# PwrSwHs1_0.net
KiCad netlist of a schematic drawn in EAGLE
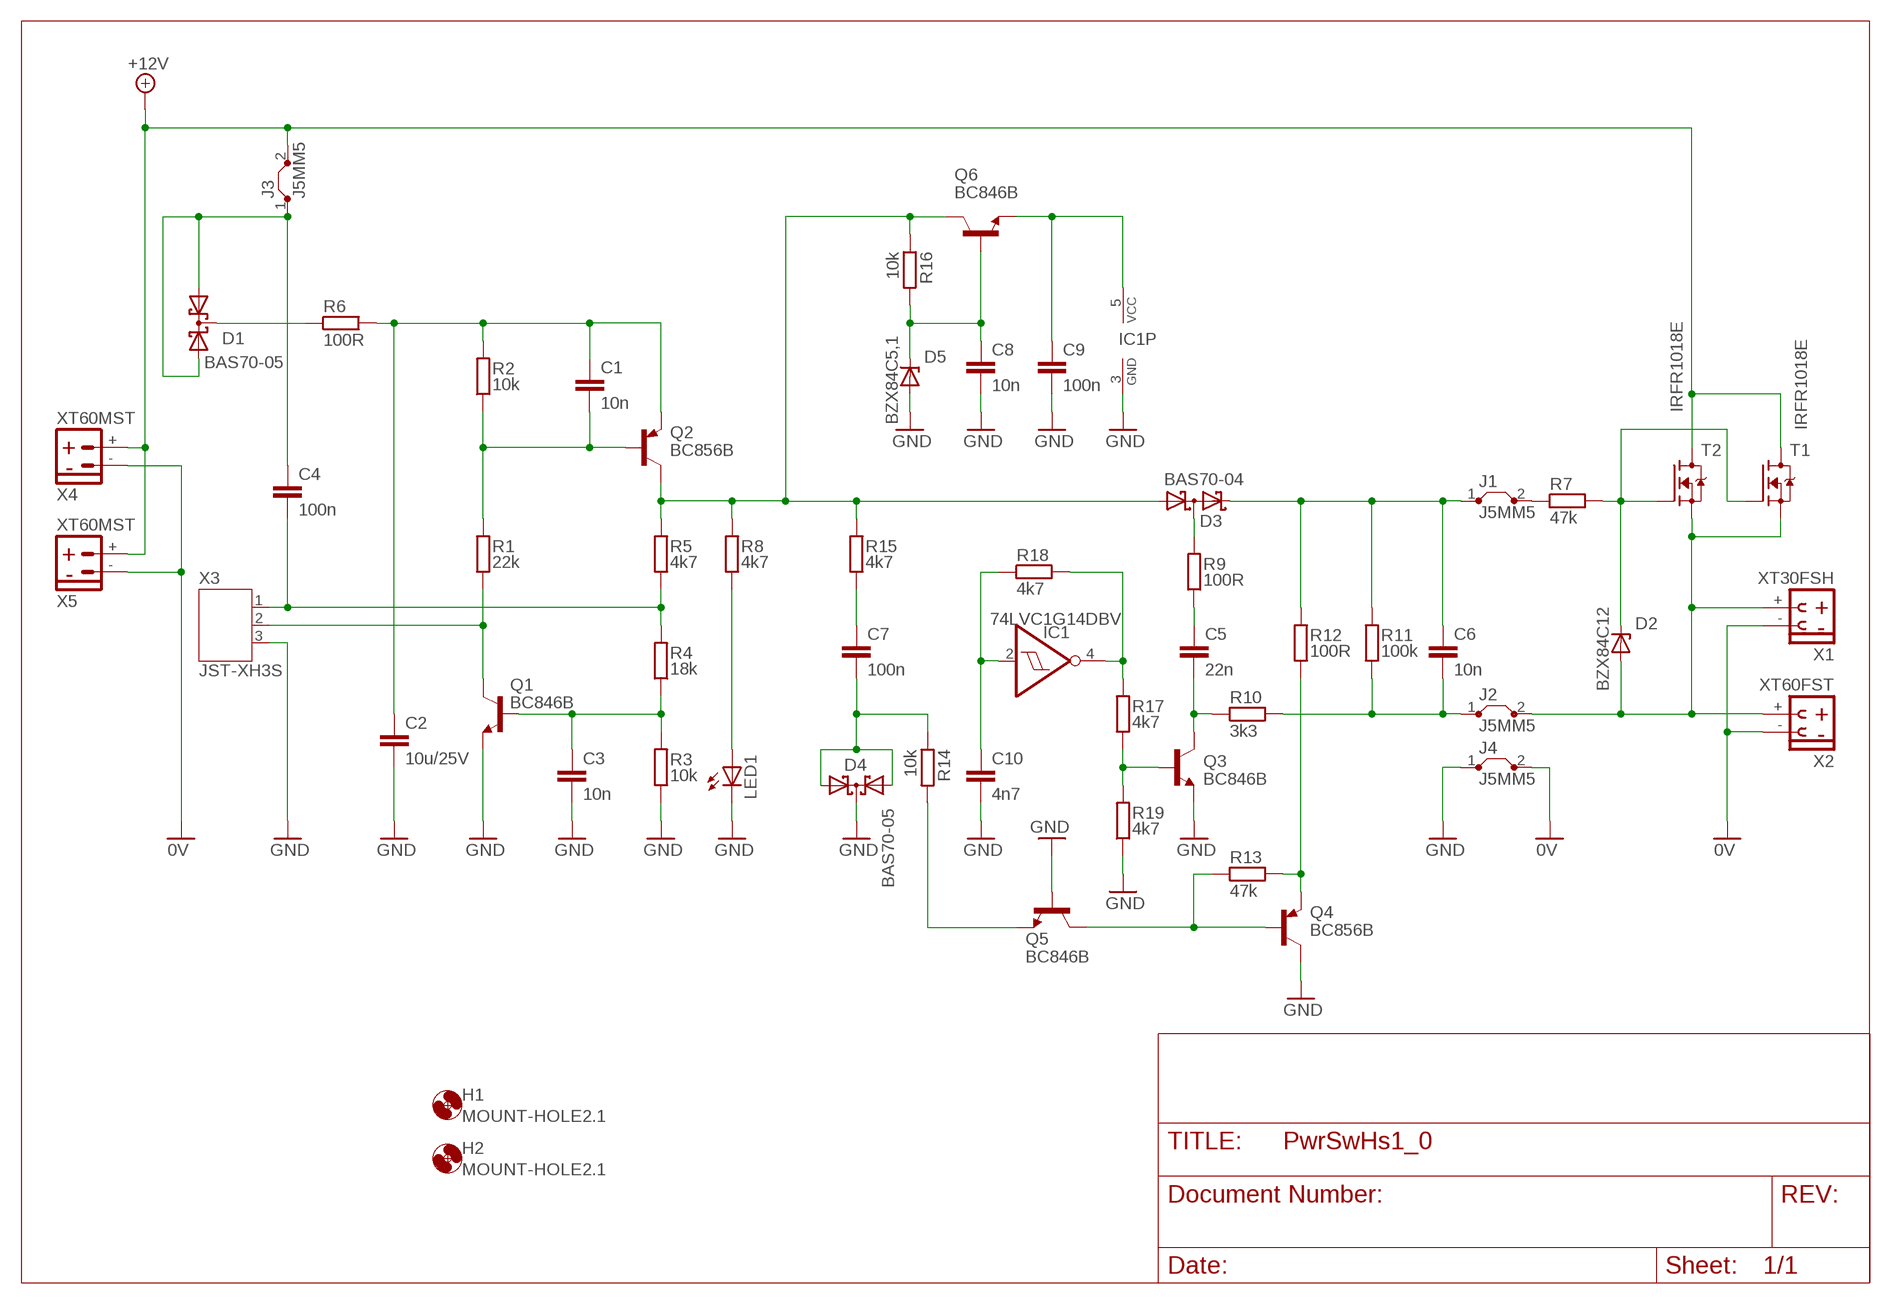
[diagram p0: schematic, sheet 1]

(export (version "E")
  (design (tool "Eeschema 10.0.6"))
  (components
    (comp (ref "C1")
      (value "10n")
      (footprint "eagle-import:C0805")
      (libsource (lib "eagle-import") (part "C-EUC0805"))
    )
    (comp (ref "C2")
      (value "10u/25V")
      (footprint "eagle-import:C1210")
      (libsource (lib "eagle-import") (part "C-EUC1210"))
    )
    (comp (ref "C3")
      (value "10n")
      (footprint "eagle-import:C0805")
      (libsource (lib "eagle-import") (part "C-EUC0805"))
    )
    (comp (ref "C4")
      (value "100n")
      (footprint "eagle-import:C0805")
      (libsource (lib "eagle-import") (part "C-EUC0805"))
    )
    (comp (ref "C5")
      (value "22n")
      (footprint "eagle-import:C0805")
      (libsource (lib "eagle-import") (part "C-EUC0805"))
    )
    (comp (ref "C6")
      (value "10n")
      (footprint "eagle-import:C0805")
      (libsource (lib "eagle-import") (part "C-EUC0805"))
    )
    (comp (ref "C7")
      (value "100n")
      (footprint "eagle-import:C0805")
      (libsource (lib "eagle-import") (part "C-EUC0805"))
    )
    (comp (ref "C8")
      (value "10n")
      (footprint "eagle-import:C0805")
      (libsource (lib "eagle-import") (part "C-EUC0805"))
    )
    (comp (ref "C9")
      (value "100n")
      (footprint "eagle-import:C0805")
      (libsource (lib "eagle-import") (part "C-EUC0805"))
    )
    (comp (ref "C10")
      (value "4n7")
      (footprint "eagle-import:C0805")
      (libsource (lib "eagle-import") (part "C-EUC0805"))
    )
    (comp (ref "D1")
      (value "BAS70-05")
      (footprint "eagle-import:SOT23")
      (libsource (lib "eagle-import") (part "BAS70-05"))
    )
    (comp (ref "D2")
      (value "BZX84C12")
      (footprint "eagle-import:TO236")
      (libsource (lib "eagle-import") (part "BZX84CSMD"))
    )
    (comp (ref "D3")
      (value "BAS70-04")
      (footprint "eagle-import:SOT23")
      (libsource (lib "eagle-import") (part "BAS70-04"))
    )
    (comp (ref "D4")
      (value "BAS70-05")
      (footprint "eagle-import:SOT23")
      (libsource (lib "eagle-import") (part "BAS70-05"))
    )
    (comp (ref "D5")
      (value "BZX84C5,1")
      (footprint "eagle-import:TO236")
      (libsource (lib "eagle-import") (part "BZX84CSMD"))
    )
    (comp (ref "H1")
      (value "MOUNT-HOLE2.1")
      (footprint "eagle-import:2,1")
      (libsource (lib "eagle-import") (part "MOUNT-HOLE2.1"))
    )
    (comp (ref "H2")
      (value "MOUNT-HOLE2.1")
      (footprint "eagle-import:2,1")
      (libsource (lib "eagle-import") (part "MOUNT-HOLE2.1"))
    )
    (comp (ref "IC1")
      (value "74LVC1G14DBV")
      (footprint "eagle-import:SOT23-5")
      (libsource (lib "eagle-import") (part "741G14DBVLVC"))
    )
    (comp (ref "J1")
      (value "J5MM5")
      (footprint "eagle-import:053")
      (libsource (lib "eagle-import") (part "J5MM5"))
    )
    (comp (ref "J2")
      (value "J5MM5")
      (footprint "eagle-import:053")
      (libsource (lib "eagle-import") (part "J5MM5"))
    )
    (comp (ref "J3")
      (value "J5MM5")
      (footprint "eagle-import:053")
      (libsource (lib "eagle-import") (part "J5MM5"))
    )
    (comp (ref "J4")
      (value "J5MM5")
      (footprint "eagle-import:053")
      (libsource (lib "eagle-import") (part "J5MM5"))
    )
    (comp (ref "LED1")
      (value "LEDLED3MML")
      (footprint "eagle-import:LED3MML")
      (libsource (lib "eagle-import") (part "LEDLED3MML"))
    )
    (comp (ref "Q1")
      (value "BC846B")
      (footprint "eagle-import:SOT23")
      (libsource (lib "eagle-import") (part "BC846SMDB"))
    )
    (comp (ref "Q2")
      (value "BC856B")
      (footprint "eagle-import:SOT23-BEC")
      (libsource (lib "eagle-import") (part "BC856SMDB"))
    )
    (comp (ref "Q3")
      (value "BC846B")
      (footprint "eagle-import:SOT23")
      (libsource (lib "eagle-import") (part "BC846SMDB"))
    )
    (comp (ref "Q4")
      (value "BC856B")
      (footprint "eagle-import:SOT23-BEC")
      (libsource (lib "eagle-import") (part "BC856SMDB"))
    )
    (comp (ref "Q5")
      (value "BC846B")
      (footprint "eagle-import:SOT23")
      (libsource (lib "eagle-import") (part "BC846SMDB"))
    )
    (comp (ref "Q6")
      (value "BC846B")
      (footprint "eagle-import:SOT23")
      (libsource (lib "eagle-import") (part "BC846SMDB"))
    )
    (comp (ref "R1")
      (value "22k")
      (footprint "eagle-import:R0805")
      (libsource (lib "eagle-import") (part "R-EU_R0805"))
    )
    (comp (ref "R2")
      (value "10k")
      (footprint "eagle-import:R0805")
      (libsource (lib "eagle-import") (part "R-EU_R0805"))
    )
    (comp (ref "R3")
      (value "10k")
      (footprint "eagle-import:R0805")
      (libsource (lib "eagle-import") (part "R-EU_R0805"))
    )
    (comp (ref "R4")
      (value "18k")
      (footprint "eagle-import:R0805")
      (libsource (lib "eagle-import") (part "R-EU_R0805"))
    )
    (comp (ref "R5")
      (value "4k7")
      (footprint "eagle-import:R0805")
      (libsource (lib "eagle-import") (part "R-EU_R0805"))
    )
    (comp (ref "R6")
      (value "100R")
      (footprint "eagle-import:R0805")
      (libsource (lib "eagle-import") (part "R-EU_R0805"))
    )
    (comp (ref "R7")
      (value "47k")
      (footprint "eagle-import:R0805")
      (libsource (lib "eagle-import") (part "R-EU_R0805"))
    )
    (comp (ref "R8")
      (value "4k7")
      (footprint "eagle-import:R0805")
      (libsource (lib "eagle-import") (part "R-EU_R0805"))
    )
    (comp (ref "R9")
      (value "100R")
      (footprint "eagle-import:R0805")
      (libsource (lib "eagle-import") (part "R-EU_R0805"))
    )
    (comp (ref "R10")
      (value "3k3")
      (footprint "eagle-import:R0805")
      (libsource (lib "eagle-import") (part "R-EU_R0805"))
    )
    (comp (ref "R11")
      (value "100k")
      (footprint "eagle-import:R0805")
      (libsource (lib "eagle-import") (part "R-EU_R0805"))
    )
    (comp (ref "R12")
      (value "100R")
      (footprint "eagle-import:R0805")
      (libsource (lib "eagle-import") (part "R-EU_R0805"))
    )
    (comp (ref "R13")
      (value "47k")
      (footprint "eagle-import:R0805")
      (libsource (lib "eagle-import") (part "R-EU_R0805"))
    )
    (comp (ref "R14")
      (value "10k")
      (footprint "eagle-import:R0805")
      (libsource (lib "eagle-import") (part "R-EU_R0805"))
    )
    (comp (ref "R15")
      (value "4k7")
      (footprint "eagle-import:R0805")
      (libsource (lib "eagle-import") (part "R-EU_R0805"))
    )
    (comp (ref "R16")
      (value "10k")
      (footprint "eagle-import:R0805")
      (libsource (lib "eagle-import") (part "R-EU_R0805"))
    )
    (comp (ref "R17")
      (value "4k7")
      (footprint "eagle-import:R0805")
      (libsource (lib "eagle-import") (part "R-EU_R0805"))
    )
    (comp (ref "R18")
      (value "4k7")
      (footprint "eagle-import:R0805")
      (libsource (lib "eagle-import") (part "R-EU_R0805"))
    )
    (comp (ref "R19")
      (value "4k7")
      (footprint "eagle-import:R0805")
      (libsource (lib "eagle-import") (part "R-EU_R0805"))
    )
    (comp (ref "T1")
      (value "IRFR1018E")
      (footprint "eagle-import:TO252")
      (libsource (lib "eagle-import") (part "MOSFET-N-CHTO252"))
    )
    (comp (ref "T2")
      (value "IRFR1018E")
      (footprint "eagle-import:TO252")
      (libsource (lib "eagle-import") (part "MOSFET-N-CHTO252"))
    )
    (comp (ref "X1")
      (value "XT30FSH")
      (footprint "eagle-import:XT30F-SH")
      (libsource (lib "eagle-import") (part "XT30FSH"))
    )
    (comp (ref "X2")
      (value "XT60FST")
      (footprint "eagle-import:XT60F-ST")
      (libsource (lib "eagle-import") (part "XT60FST"))
    )
    (comp (ref "X3")
      (value "JST-XH3S")
      (footprint "eagle-import:JST-XH3SMD")
      (libsource (lib "eagle-import") (part "JST-XH3S"))
    )
    (comp (ref "X4")
      (value "XT60MST")
      (footprint "eagle-import:XT60M-ST")
      (libsource (lib "eagle-import") (part "XT60MST"))
    )
    (comp (ref "X5")
      (value "XT60MST")
      (footprint "eagle-import:XT60M-ST")
      (libsource (lib "eagle-import") (part "XT60MST"))
    )
  )
  (nets
    (net (code "1") (name "+12V") (class "Default")
      (node (ref "J3") (pin "2") (pinfunction "2_2") (pintype "passive"))
      (node (ref "T1") (pin "3") (pinfunction "D_3") (pintype "passive"))
      (node (ref "T2") (pin "3") (pinfunction "D_3") (pintype "passive"))
      (node (ref "X4") (pin "+") (pinfunction "+_+") (pintype "passive"))
      (node (ref "X5") (pin "+") (pinfunction "+_+") (pintype "passive"))
    )
    (net (code "2") (name "0V") (class "Default")
      (node (ref "J4") (pin "2") (pinfunction "2_2") (pintype "passive"))
      (node (ref "X1") (pin "-") (pinfunction "-_-") (pintype "passive"))
      (node (ref "X2") (pin "-") (pinfunction "-_-") (pintype "passive"))
      (node (ref "X4") (pin "-") (pinfunction "-_-") (pintype "passive"))
      (node (ref "X5") (pin "-") (pinfunction "-_-") (pintype "passive"))
    )
    (net (code "3") (name "GND") (class "Default")
      (node (ref "C10") (pin "2") (pinfunction "2_2") (pintype "passive"))
      (node (ref "C2") (pin "2") (pinfunction "2_2") (pintype "passive"))
      (node (ref "C3") (pin "2") (pinfunction "2_2") (pintype "passive"))
      (node (ref "C8") (pin "2") (pinfunction "2_2") (pintype "passive"))
      (node (ref "C9") (pin "2") (pinfunction "2_2") (pintype "passive"))
      (node (ref "D4") (pin "3") (pinfunction "C_3") (pintype "passive"))
      (node (ref "D5") (pin "A") (pinfunction "A_A") (pintype "passive"))
      (node (ref "IC1") (pin "3") (pinfunction "GND_3") (pintype "power_in"))
      (node (ref "J4") (pin "1") (pinfunction "1_1") (pintype "passive"))
      (node (ref "LED1") (pin "K") (pinfunction "C_K") (pintype "passive"))
      (node (ref "Q1") (pin "2") (pinfunction "E_2") (pintype "passive"))
      (node (ref "Q3") (pin "2") (pinfunction "E_2") (pintype "passive"))
      (node (ref "Q4") (pin "C") (pinfunction "C_C") (pintype "passive"))
      (node (ref "Q5") (pin "1") (pinfunction "B_1") (pintype "passive"))
      (node (ref "R19") (pin "1") (pinfunction "1_1") (pintype "passive"))
      (node (ref "R3") (pin "1") (pinfunction "1_1") (pintype "passive"))
      (node (ref "X3") (pin "3") (pinfunction "3_3") (pintype "passive"))
    )
    (net (code "4") (name "Net-(C1-Pad1)") (class "Default")
      (node (ref "C1") (pin "1") (pinfunction "1_1") (pintype "passive"))
      (node (ref "C2") (pin "1") (pinfunction "1_1") (pintype "passive"))
      (node (ref "Q2") (pin "E") (pinfunction "E_E") (pintype "passive"))
      (node (ref "R2") (pin "2") (pinfunction "2_2") (pintype "passive"))
      (node (ref "R6") (pin "2") (pinfunction "2_2") (pintype "passive"))
    )
    (net (code "5") (name "Net-(C1-Pad2)") (class "Default")
      (node (ref "C1") (pin "2") (pinfunction "2_2") (pintype "passive"))
      (node (ref "Q2") (pin "B") (pinfunction "B_B") (pintype "passive"))
      (node (ref "R1") (pin "2") (pinfunction "2_2") (pintype "passive"))
      (node (ref "R2") (pin "1") (pinfunction "1_1") (pintype "passive"))
    )
    (net (code "6") (name "Net-(C4-Pad2)") (class "Default")
      (node (ref "C4") (pin "2") (pinfunction "2_2") (pintype "passive"))
      (node (ref "R4") (pin "2") (pinfunction "2_2") (pintype "passive"))
      (node (ref "R5") (pin "1") (pinfunction "1_1") (pintype "passive"))
      (node (ref "X3") (pin "1") (pinfunction "1_1") (pintype "passive"))
    )
    (net (code "7") (name "Net-(C5-Pad1)") (class "Default")
      (node (ref "C5") (pin "1") (pinfunction "1_1") (pintype "passive"))
      (node (ref "R9") (pin "1") (pinfunction "1_1") (pintype "passive"))
    )
    (net (code "8") (name "Net-(C6-Pad2)") (class "Default")
      (node (ref "C6") (pin "2") (pinfunction "2_2") (pintype "passive"))
      (node (ref "J2") (pin "1") (pinfunction "1_1") (pintype "passive"))
      (node (ref "R10") (pin "2") (pinfunction "2_2") (pintype "passive"))
      (node (ref "R11") (pin "1") (pinfunction "1_1") (pintype "passive"))
    )
    (net (code "9") (name "Net-(C7-Pad1)") (class "Default")
      (node (ref "C7") (pin "1") (pinfunction "1_1") (pintype "passive"))
      (node (ref "R15") (pin "1") (pinfunction "1_1") (pintype "passive"))
    )
    (net (code "10") (name "Net-(D1-A1)") (class "Default")
      (node (ref "C4") (pin "1") (pinfunction "1_1") (pintype "passive"))
      (node (ref "D1") (pin "1") (pinfunction "A1_1") (pintype "passive"))
      (node (ref "D1") (pin "2") (pinfunction "A2_2") (pintype "passive"))
      (node (ref "J3") (pin "1") (pinfunction "1_1") (pintype "passive"))
    )
    (net (code "11") (name "Net-(D1-C)") (class "Default")
      (node (ref "D1") (pin "3") (pinfunction "C_3") (pintype "passive"))
      (node (ref "R6") (pin "1") (pinfunction "1_1") (pintype "passive"))
    )
    (net (code "12") (name "Net-(D3-A1)") (class "Default")
      (node (ref "D3") (pin "1") (pinfunction "A1_1") (pintype "passive"))
      (node (ref "Q2") (pin "C") (pinfunction "C_C") (pintype "passive"))
      (node (ref "Q6") (pin "3") (pinfunction "C_3") (pintype "passive"))
      (node (ref "R15") (pin "2") (pinfunction "2_2") (pintype "passive"))
      (node (ref "R16") (pin "1") (pinfunction "1_1") (pintype "passive"))
      (node (ref "R5") (pin "2") (pinfunction "2_2") (pintype "passive"))
      (node (ref "R8") (pin "2") (pinfunction "2_2") (pintype "passive"))
    )
    (net (code "13") (name "Net-(D3-C1A2)") (class "Default")
      (node (ref "D3") (pin "3") (pinfunction "C1A2_3") (pintype "passive"))
      (node (ref "R9") (pin "2") (pinfunction "2_2") (pintype "passive"))
    )
    (net (code "14") (name "Net-(D3-C2)") (class "Default")
      (node (ref "C6") (pin "1") (pinfunction "1_1") (pintype "passive"))
      (node (ref "D3") (pin "2") (pinfunction "C2_2") (pintype "passive"))
      (node (ref "J1") (pin "1") (pinfunction "1_1") (pintype "passive"))
      (node (ref "R11") (pin "2") (pinfunction "2_2") (pintype "passive"))
      (node (ref "R12") (pin "2") (pinfunction "2_2") (pintype "passive"))
    )
    (net (code "15") (name "Net-(D4-A1)") (class "Default")
      (node (ref "C7") (pin "2") (pinfunction "2_2") (pintype "passive"))
      (node (ref "D4") (pin "1") (pinfunction "A1_1") (pintype "passive"))
      (node (ref "D4") (pin "2") (pinfunction "A2_2") (pintype "passive"))
      (node (ref "R14") (pin "1") (pinfunction "1_1") (pintype "passive"))
    )
    (net (code "16") (name "Net-(IC1A-I)") (class "Default")
      (node (ref "C10") (pin "1") (pinfunction "1_1") (pintype "passive"))
      (node (ref "IC1") (pin "2") (pinfunction "I_2") (pintype "input"))
      (node (ref "R18") (pin "1") (pinfunction "1_1") (pintype "passive"))
    )
    (net (code "17") (name "Net-(IC1A-O)") (class "Default")
      (node (ref "IC1") (pin "4") (pinfunction "O_4") (pintype "output"))
      (node (ref "R17") (pin "2") (pinfunction "2_2") (pintype "passive"))
      (node (ref "R18") (pin "2") (pinfunction "2_2") (pintype "passive"))
    )
    (net (code "18") (name "Net-(IC1B-VCC)") (class "Default")
      (node (ref "C9") (pin "1") (pinfunction "1_1") (pintype "passive"))
      (node (ref "IC1") (pin "5") (pinfunction "VCC_5") (pintype "power_in"))
      (node (ref "Q6") (pin "2") (pinfunction "E_2") (pintype "passive"))
    )
    (net (code "19") (name "Net-(J1-Pad2)") (class "Default")
      (node (ref "J1") (pin "2") (pinfunction "2_2") (pintype "passive"))
      (node (ref "R7") (pin "1") (pinfunction "1_1") (pintype "passive"))
    )
    (net (code "20") (name "Net-(LED1-PadA)") (class "Default")
      (node (ref "LED1") (pin "A") (pinfunction "A_A") (pintype "passive"))
      (node (ref "R8") (pin "1") (pinfunction "1_1") (pintype "passive"))
    )
    (net (code "21") (name "Net-(Q1-B)") (class "Default")
      (node (ref "C3") (pin "1") (pinfunction "1_1") (pintype "passive"))
      (node (ref "Q1") (pin "1") (pinfunction "B_1") (pintype "passive"))
      (node (ref "R3") (pin "2") (pinfunction "2_2") (pintype "passive"))
      (node (ref "R4") (pin "1") (pinfunction "1_1") (pintype "passive"))
    )
    (net (code "22") (name "Net-(Q1-C)") (class "Default")
      (node (ref "Q1") (pin "3") (pinfunction "C_3") (pintype "passive"))
      (node (ref "R1") (pin "1") (pinfunction "1_1") (pintype "passive"))
      (node (ref "X3") (pin "2") (pinfunction "2_2") (pintype "passive"))
    )
    (net (code "23") (name "Net-(Q3-B)") (class "Default")
      (node (ref "Q3") (pin "1") (pinfunction "B_1") (pintype "passive"))
      (node (ref "R17") (pin "1") (pinfunction "1_1") (pintype "passive"))
      (node (ref "R19") (pin "2") (pinfunction "2_2") (pintype "passive"))
    )
    (net (code "24") (name "Net-(Q3-C)") (class "Default")
      (node (ref "C5") (pin "2") (pinfunction "2_2") (pintype "passive"))
      (node (ref "Q3") (pin "3") (pinfunction "C_3") (pintype "passive"))
      (node (ref "R10") (pin "1") (pinfunction "1_1") (pintype "passive"))
    )
    (net (code "25") (name "Net-(Q4-PadE)") (class "Default")
      (node (ref "Q4") (pin "E") (pinfunction "E_E") (pintype "passive"))
      (node (ref "R12") (pin "1") (pinfunction "1_1") (pintype "passive"))
      (node (ref "R13") (pin "2") (pinfunction "2_2") (pintype "passive"))
    )
    (net (code "26") (name "Net-(Q5-C)") (class "Default")
      (node (ref "Q4") (pin "B") (pinfunction "B_B") (pintype "passive"))
      (node (ref "Q5") (pin "3") (pinfunction "C_3") (pintype "passive"))
      (node (ref "R13") (pin "1") (pinfunction "1_1") (pintype "passive"))
    )
    (net (code "27") (name "Net-(Q5-E)") (class "Default")
      (node (ref "Q5") (pin "2") (pinfunction "E_2") (pintype "passive"))
      (node (ref "R14") (pin "2") (pinfunction "2_2") (pintype "passive"))
    )
    (net (code "28") (name "Net-(Q6-B)") (class "Default")
      (node (ref "C8") (pin "1") (pinfunction "1_1") (pintype "passive"))
      (node (ref "D5") (pin "C") (pinfunction "C_C") (pintype "passive"))
      (node (ref "Q6") (pin "1") (pinfunction "B_1") (pintype "passive"))
      (node (ref "R16") (pin "2") (pinfunction "2_2") (pintype "passive"))
    )
    (net (code "29") (name "Net-(T1-G)") (class "Default")
      (node (ref "D2") (pin "C") (pinfunction "C_C") (pintype "passive"))
      (node (ref "R7") (pin "2") (pinfunction "2_2") (pintype "passive"))
      (node (ref "T1") (pin "1") (pinfunction "G_1") (pintype "passive"))
      (node (ref "T2") (pin "1") (pinfunction "G_1") (pintype "passive"))
    )
    (net (code "30") (name "Net-(T1-S)") (class "Default")
      (node (ref "D2") (pin "A") (pinfunction "A_A") (pintype "passive"))
      (node (ref "J2") (pin "2") (pinfunction "2_2") (pintype "passive"))
      (node (ref "T1") (pin "2") (pinfunction "S_2") (pintype "passive"))
      (node (ref "T2") (pin "2") (pinfunction "S_2") (pintype "passive"))
      (node (ref "X1") (pin "+") (pinfunction "+_+") (pintype "passive"))
      (node (ref "X2") (pin "+") (pinfunction "+_+") (pintype "passive"))
    )
  )
)
